# HumTx.net
KiCad netlist of a schematic drawn in EAGLE
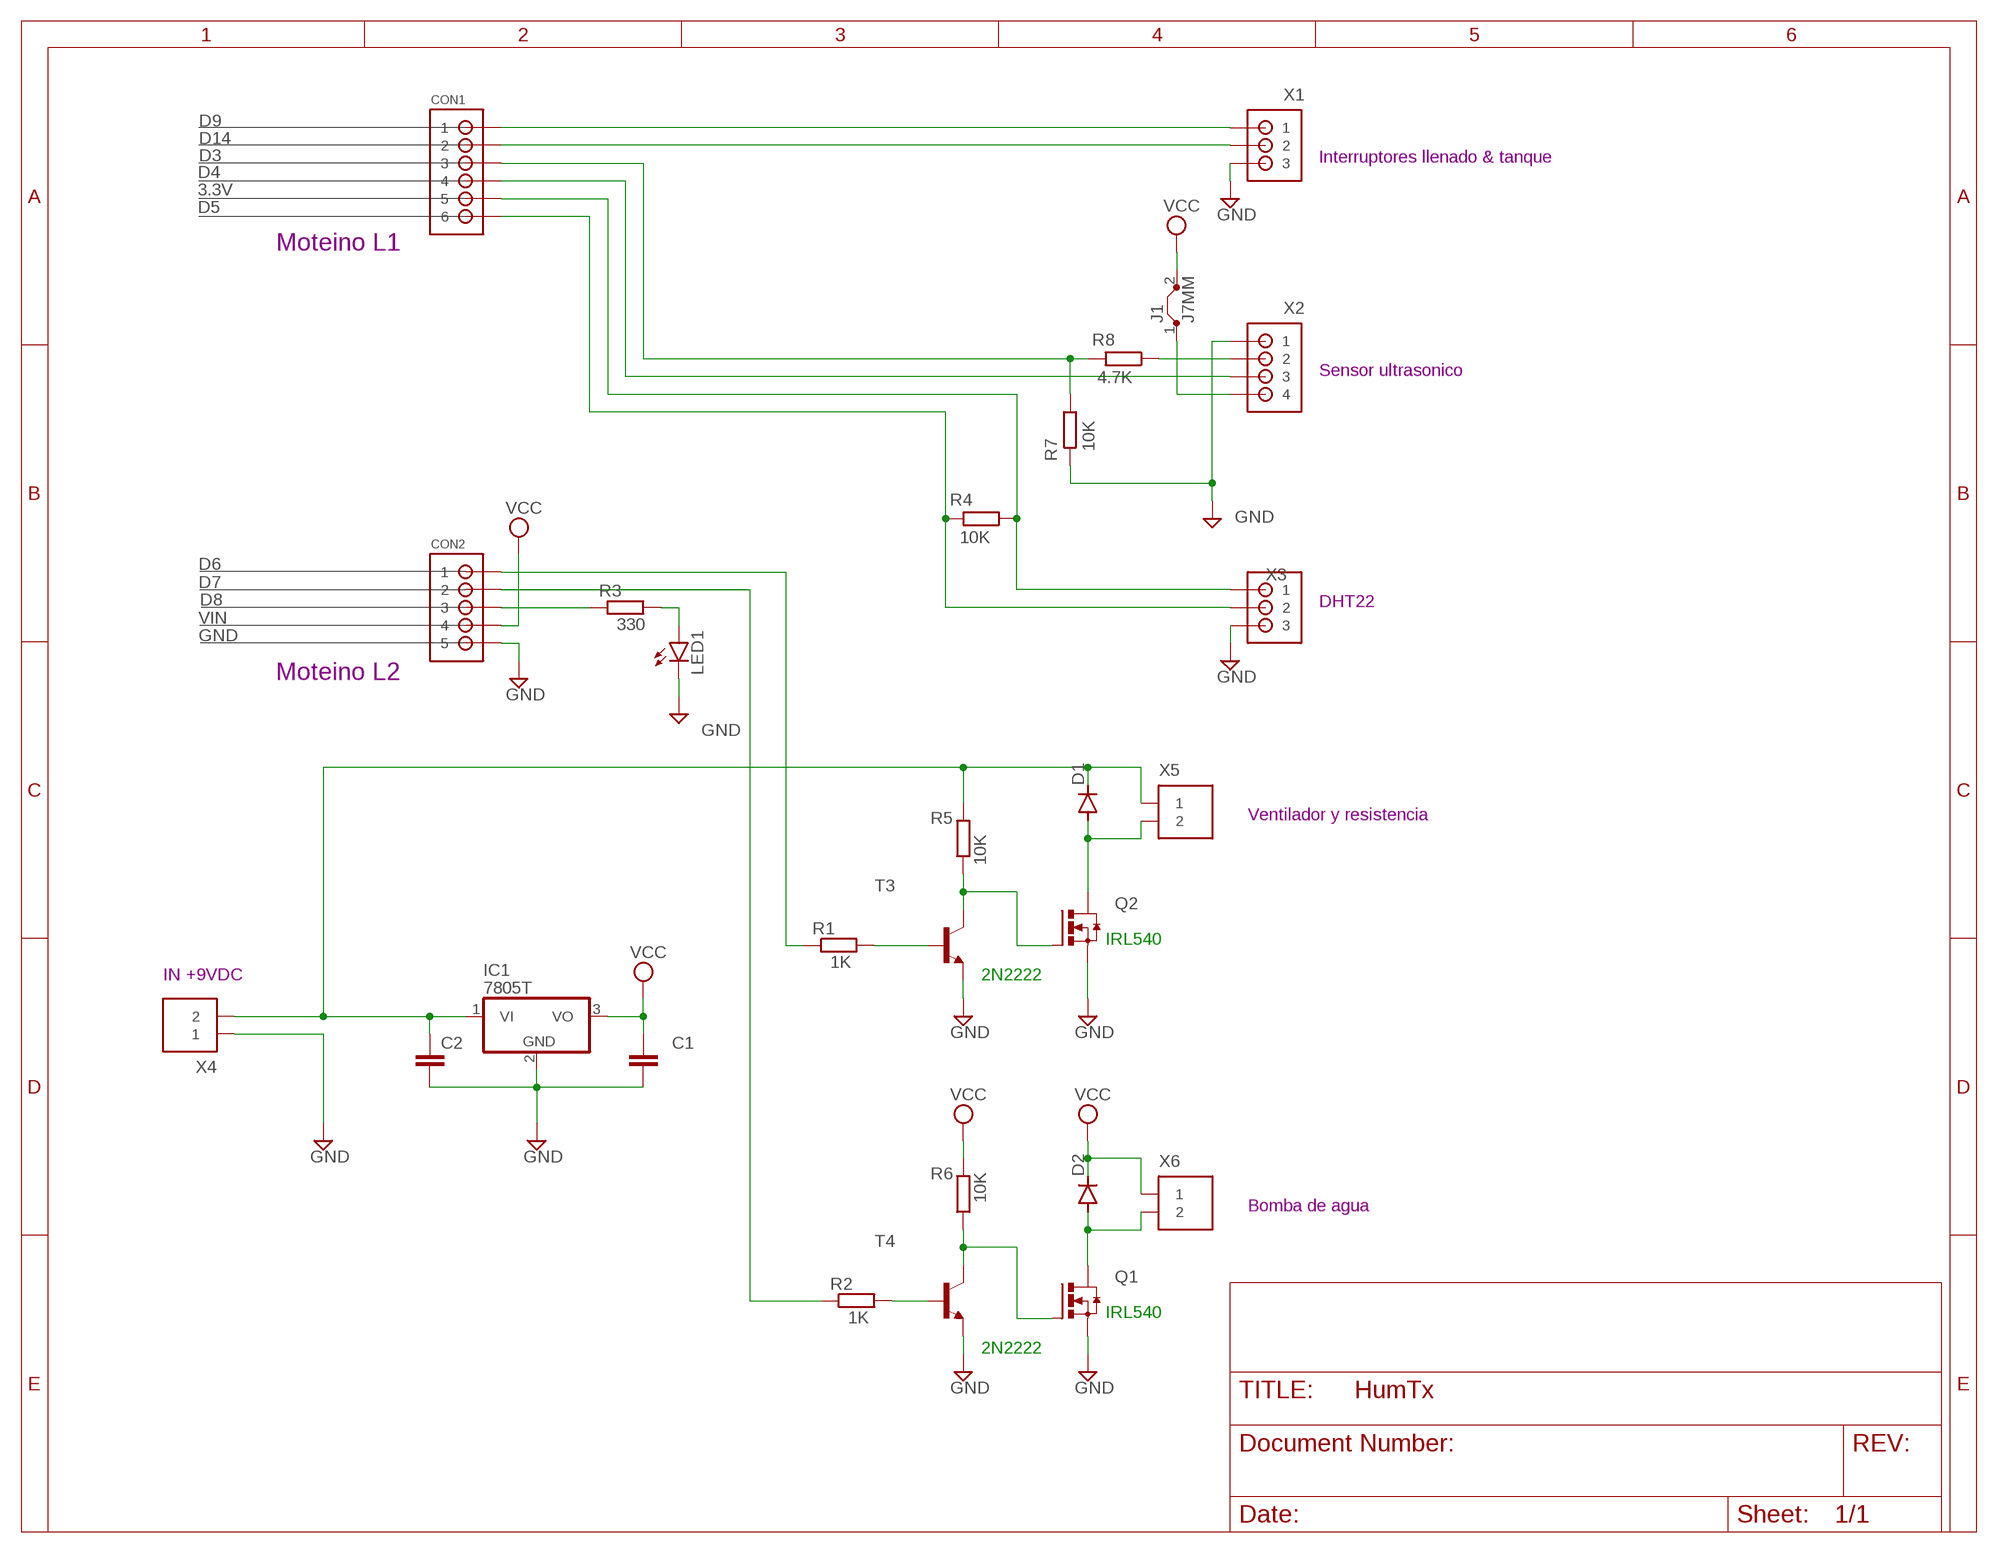
[diagram p0: schematic, sheet 1]

(export (version "E")
  (design (tool "Eeschema 10.0.6"))
  (components
    (comp (ref "C1")
      (value "C5/7.2")
      (footprint "eagle-import:C5B7.2")
      (libsource (lib "eagle-import") (part "C5/7.2"))
    )
    (comp (ref "C2")
      (value "C5/7.2")
      (footprint "eagle-import:C5B7.2")
      (libsource (lib "eagle-import") (part "C5/7.2"))
    )
    (comp (ref "CON1")
      (value "B6B-ZR")
      (footprint "eagle-import:B6B-ZR")
      (libsource (lib "eagle-import") (part "B6B-ZR"))
    )
    (comp (ref "CON2")
      (value "B5B-ZR")
      (footprint "eagle-import:B5B-ZR")
      (libsource (lib "eagle-import") (part "B5B-ZR"))
    )
    (comp (ref "D1")
      (value "1N4004")
      (footprint "eagle-import:DO41-10")
      (libsource (lib "eagle-import") (part "1N4004"))
    )
    (comp (ref "D2")
      (value "1N4004")
      (footprint "eagle-import:DO41-10")
      (libsource (lib "eagle-import") (part "1N4004"))
    )
    (comp (ref "IC1")
      (value "7805T")
      (footprint "eagle-import:TO220H")
      (libsource (lib "eagle-import") (part "78T05"))
    )
    (comp (ref "J1")
      (value "J7MM")
      (footprint "eagle-import:07")
      (libsource (lib "eagle-import") (part "J7MM"))
    )
    (comp (ref "LED1")
      (value "LED5MM")
      (footprint "eagle-import:LED5MM")
      (libsource (lib "eagle-import") (part "LED5MM"))
    )
    (comp (ref "Q1")
      (value "IRF3704-H")
      (footprint "eagle-import:TO220BH")
      (libsource (lib "eagle-import") (part "IRF3704-H"))
    )
    (comp (ref "Q2")
      (value "IRF3704-H")
      (footprint "eagle-import:TO220BH")
      (libsource (lib "eagle-import") (part "IRF3704-H"))
    )
    (comp (ref "R1")
      (value "1K")
      (footprint "eagle-import:0207_10")
      (libsource (lib "eagle-import") (part "R0207/10"))
    )
    (comp (ref "R2")
      (value "1K")
      (footprint "eagle-import:0207_10")
      (libsource (lib "eagle-import") (part "R0207/10"))
    )
    (comp (ref "R3")
      (value "330")
      (footprint "eagle-import:0207_10")
      (libsource (lib "eagle-import") (part "R0207/10"))
    )
    (comp (ref "R4")
      (value "10K")
      (footprint "eagle-import:0207_10")
      (libsource (lib "eagle-import") (part "R0207/10"))
    )
    (comp (ref "R5")
      (value "10K")
      (footprint "eagle-import:0204_7")
      (libsource (lib "eagle-import") (part "R0204/7"))
    )
    (comp (ref "R6")
      (value "10K")
      (footprint "eagle-import:0204_7")
      (libsource (lib "eagle-import") (part "R0204/7"))
    )
    (comp (ref "R7")
      (value "10K")
      (footprint "eagle-import:0207_10")
      (libsource (lib "eagle-import") (part "R0207/10"))
    )
    (comp (ref "R8")
      (value "4.7K")
      (footprint "eagle-import:0207_10")
      (libsource (lib "eagle-import") (part "R0207/10"))
    )
    (comp (ref "T3")
      (value "-NPN-TO92-EBC")
      (footprint "eagle-import:TO92-EBC")
      (libsource (lib "eagle-import") (part "-NPN-TO92-EBC"))
    )
    (comp (ref "T4")
      (value "-NPN-TO92-EBC")
      (footprint "eagle-import:TO92-EBC")
      (libsource (lib "eagle-import") (part "-NPN-TO92-EBC"))
    )
    (comp (ref "X1")
      (value "B3B-ZR")
      (footprint "eagle-import:B3B-ZR")
      (libsource (lib "eagle-import") (part "B3B-ZR"))
    )
    (comp (ref "X2")
      (value "B4B-ZR")
      (footprint "eagle-import:B4B-ZR")
      (libsource (lib "eagle-import") (part "B4B-ZR"))
    )
    (comp (ref "X3")
      (value "B3B-ZR")
      (footprint "eagle-import:B3B-ZR")
      (libsource (lib "eagle-import") (part "B3B-ZR"))
    )
    (comp (ref "X4")
      (value "MKS1852-6-0-202")
      (footprint "eagle-import:MKS1852-6-0-202")
      (libsource (lib "eagle-import") (part "MKS1852-6-0-202"))
    )
    (comp (ref "X5")
      (value "MKS1852-6-0-202")
      (footprint "eagle-import:MKS1852-6-0-202")
      (libsource (lib "eagle-import") (part "MKS1852-6-0-202"))
    )
    (comp (ref "X6")
      (value "MKS1852-6-0-202")
      (footprint "eagle-import:MKS1852-6-0-202")
      (libsource (lib "eagle-import") (part "MKS1852-6-0-202"))
    )
  )
  (nets
    (net (code "1") (name "GND") (class "Default")
      (node (ref "C1") (pin "2") (pinfunction "2_2") (pintype "passive"))
      (node (ref "C2") (pin "2") (pinfunction "2_2") (pintype "passive"))
      (node (ref "CON2") (pin "5") (pinfunction "5_5") (pintype "bidirectional"))
      (node (ref "IC1") (pin "2") (pinfunction "GND_2") (pintype "passive"))
      (node (ref "LED1") (pin "K") (pinfunction "C_K") (pintype "passive"))
      (node (ref "Q1") (pin "S") (pinfunction "S_S") (pintype "passive"))
      (node (ref "Q2") (pin "S") (pinfunction "S_S") (pintype "passive"))
      (node (ref "R7") (pin "2") (pinfunction "2_2") (pintype "passive"))
      (node (ref "T3") (pin "E") (pinfunction "E_E") (pintype "passive"))
      (node (ref "T4") (pin "E") (pinfunction "E_E") (pintype "passive"))
      (node (ref "X1") (pin "3") (pinfunction "3_3") (pintype "bidirectional"))
      (node (ref "X2") (pin "1") (pinfunction "1_1") (pintype "bidirectional"))
      (node (ref "X3") (pin "3") (pinfunction "3_3") (pintype "bidirectional"))
      (node (ref "X4") (pin "1") (pinfunction "1_1") (pintype "input"))
    )
    (net (code "2") (name "Net-(CON1-Pad1)") (class "Default")
      (node (ref "CON1") (pin "1") (pinfunction "1_1") (pintype "bidirectional"))
      (node (ref "X1") (pin "1") (pinfunction "1_1") (pintype "bidirectional"))
    )
    (net (code "3") (name "Net-(CON1-Pad2)") (class "Default")
      (node (ref "CON1") (pin "2") (pinfunction "2_2") (pintype "bidirectional"))
      (node (ref "X1") (pin "2") (pinfunction "2_2") (pintype "bidirectional"))
    )
    (net (code "4") (name "Net-(CON1-Pad3)") (class "Default")
      (node (ref "CON1") (pin "3") (pinfunction "3_3") (pintype "bidirectional"))
      (node (ref "R7") (pin "1") (pinfunction "1_1") (pintype "passive"))
      (node (ref "R8") (pin "2") (pinfunction "2_2") (pintype "passive"))
    )
    (net (code "5") (name "Net-(CON1-Pad4)") (class "Default")
      (node (ref "CON1") (pin "4") (pinfunction "4_4") (pintype "bidirectional"))
      (node (ref "X2") (pin "3") (pinfunction "3_3") (pintype "bidirectional"))
    )
    (net (code "6") (name "Net-(CON1-Pad5)") (class "Default")
      (node (ref "CON1") (pin "5") (pinfunction "5_5") (pintype "bidirectional"))
      (node (ref "R4") (pin "1") (pinfunction "1_1") (pintype "passive"))
      (node (ref "X3") (pin "1") (pinfunction "1_1") (pintype "bidirectional"))
    )
    (net (code "7") (name "Net-(CON1-Pad6)") (class "Default")
      (node (ref "CON1") (pin "6") (pinfunction "6_6") (pintype "bidirectional"))
      (node (ref "R4") (pin "2") (pinfunction "2_2") (pintype "passive"))
      (node (ref "X3") (pin "2") (pinfunction "2_2") (pintype "bidirectional"))
    )
    (net (code "8") (name "Net-(CON2-Pad1)") (class "Default")
      (node (ref "CON2") (pin "1") (pinfunction "1_1") (pintype "bidirectional"))
      (node (ref "R1") (pin "1") (pinfunction "1_1") (pintype "passive"))
    )
    (net (code "9") (name "Net-(CON2-Pad2)") (class "Default")
      (node (ref "CON2") (pin "2") (pinfunction "2_2") (pintype "bidirectional"))
      (node (ref "R2") (pin "1") (pinfunction "1_1") (pintype "passive"))
    )
    (net (code "10") (name "Net-(CON2-Pad3)") (class "Default")
      (node (ref "CON2") (pin "3") (pinfunction "3_3") (pintype "bidirectional"))
      (node (ref "R3") (pin "1") (pinfunction "1_1") (pintype "passive"))
    )
    (net (code "11") (name "Net-(D1-PadA)") (class "Default")
      (node (ref "D1") (pin "A") (pinfunction "A_A") (pintype "passive"))
      (node (ref "Q2") (pin "D") (pinfunction "D_D") (pintype "passive"))
      (node (ref "X5") (pin "2") (pinfunction "2_2") (pintype "input"))
    )
    (net (code "12") (name "Net-(D2-PadA)") (class "Default")
      (node (ref "D2") (pin "A") (pinfunction "A_A") (pintype "passive"))
      (node (ref "Q1") (pin "D") (pinfunction "D_D") (pintype "passive"))
      (node (ref "X6") (pin "2") (pinfunction "2_2") (pintype "input"))
    )
    (net (code "13") (name "Net-(IC1-VI)") (class "Default")
      (node (ref "C2") (pin "1") (pinfunction "1_1") (pintype "passive"))
      (node (ref "D1") (pin "C") (pinfunction "C_C") (pintype "passive"))
      (node (ref "IC1") (pin "1") (pinfunction "VI_1") (pintype "input"))
      (node (ref "R5") (pin "2") (pinfunction "2_2") (pintype "passive"))
      (node (ref "X4") (pin "2") (pinfunction "2_2") (pintype "input"))
      (node (ref "X5") (pin "1") (pinfunction "1_1") (pintype "input"))
    )
    (net (code "14") (name "Net-(J1-Pad1)") (class "Default")
      (node (ref "J1") (pin "1") (pinfunction "1_1") (pintype "passive"))
      (node (ref "X2") (pin "4") (pinfunction "4_4") (pintype "bidirectional"))
    )
    (net (code "15") (name "Net-(LED1-PadA)") (class "Default")
      (node (ref "LED1") (pin "A") (pinfunction "A_A") (pintype "passive"))
      (node (ref "R3") (pin "2") (pinfunction "2_2") (pintype "passive"))
    )
    (net (code "16") (name "Net-(Q1-PadG)") (class "Default")
      (node (ref "Q1") (pin "G") (pinfunction "G_G") (pintype "passive"))
      (node (ref "R6") (pin "1") (pinfunction "1_1") (pintype "passive"))
      (node (ref "T4") (pin "C") (pinfunction "C_C") (pintype "passive"))
    )
    (net (code "17") (name "Net-(Q2-PadG)") (class "Default")
      (node (ref "Q2") (pin "G") (pinfunction "G_G") (pintype "passive"))
      (node (ref "R5") (pin "1") (pinfunction "1_1") (pintype "passive"))
      (node (ref "T3") (pin "C") (pinfunction "C_C") (pintype "passive"))
    )
    (net (code "18") (name "Net-(R1-Pad2)") (class "Default")
      (node (ref "R1") (pin "2") (pinfunction "2_2") (pintype "passive"))
      (node (ref "T3") (pin "B") (pinfunction "B_B") (pintype "passive"))
    )
    (net (code "19") (name "Net-(R2-Pad2)") (class "Default")
      (node (ref "R2") (pin "2") (pinfunction "2_2") (pintype "passive"))
      (node (ref "T4") (pin "B") (pinfunction "B_B") (pintype "passive"))
    )
    (net (code "20") (name "Net-(R8-Pad1)") (class "Default")
      (node (ref "R8") (pin "1") (pinfunction "1_1") (pintype "passive"))
      (node (ref "X2") (pin "2") (pinfunction "2_2") (pintype "bidirectional"))
    )
    (net (code "21") (name "VCC") (class "Default")
      (node (ref "C1") (pin "1") (pinfunction "1_1") (pintype "passive"))
      (node (ref "CON2") (pin "4") (pinfunction "4_4") (pintype "bidirectional"))
      (node (ref "D2") (pin "C") (pinfunction "C_C") (pintype "passive"))
      (node (ref "IC1") (pin "3") (pinfunction "VO_3") (pintype "passive"))
      (node (ref "J1") (pin "2") (pinfunction "2_2") (pintype "passive"))
      (node (ref "R6") (pin "2") (pinfunction "2_2") (pintype "passive"))
      (node (ref "X6") (pin "1") (pinfunction "1_1") (pintype "input"))
    )
  )
)
